# bolid-power-dcdc-ldo.net
KiCad netlist of a schematic drawn in Altium Designer
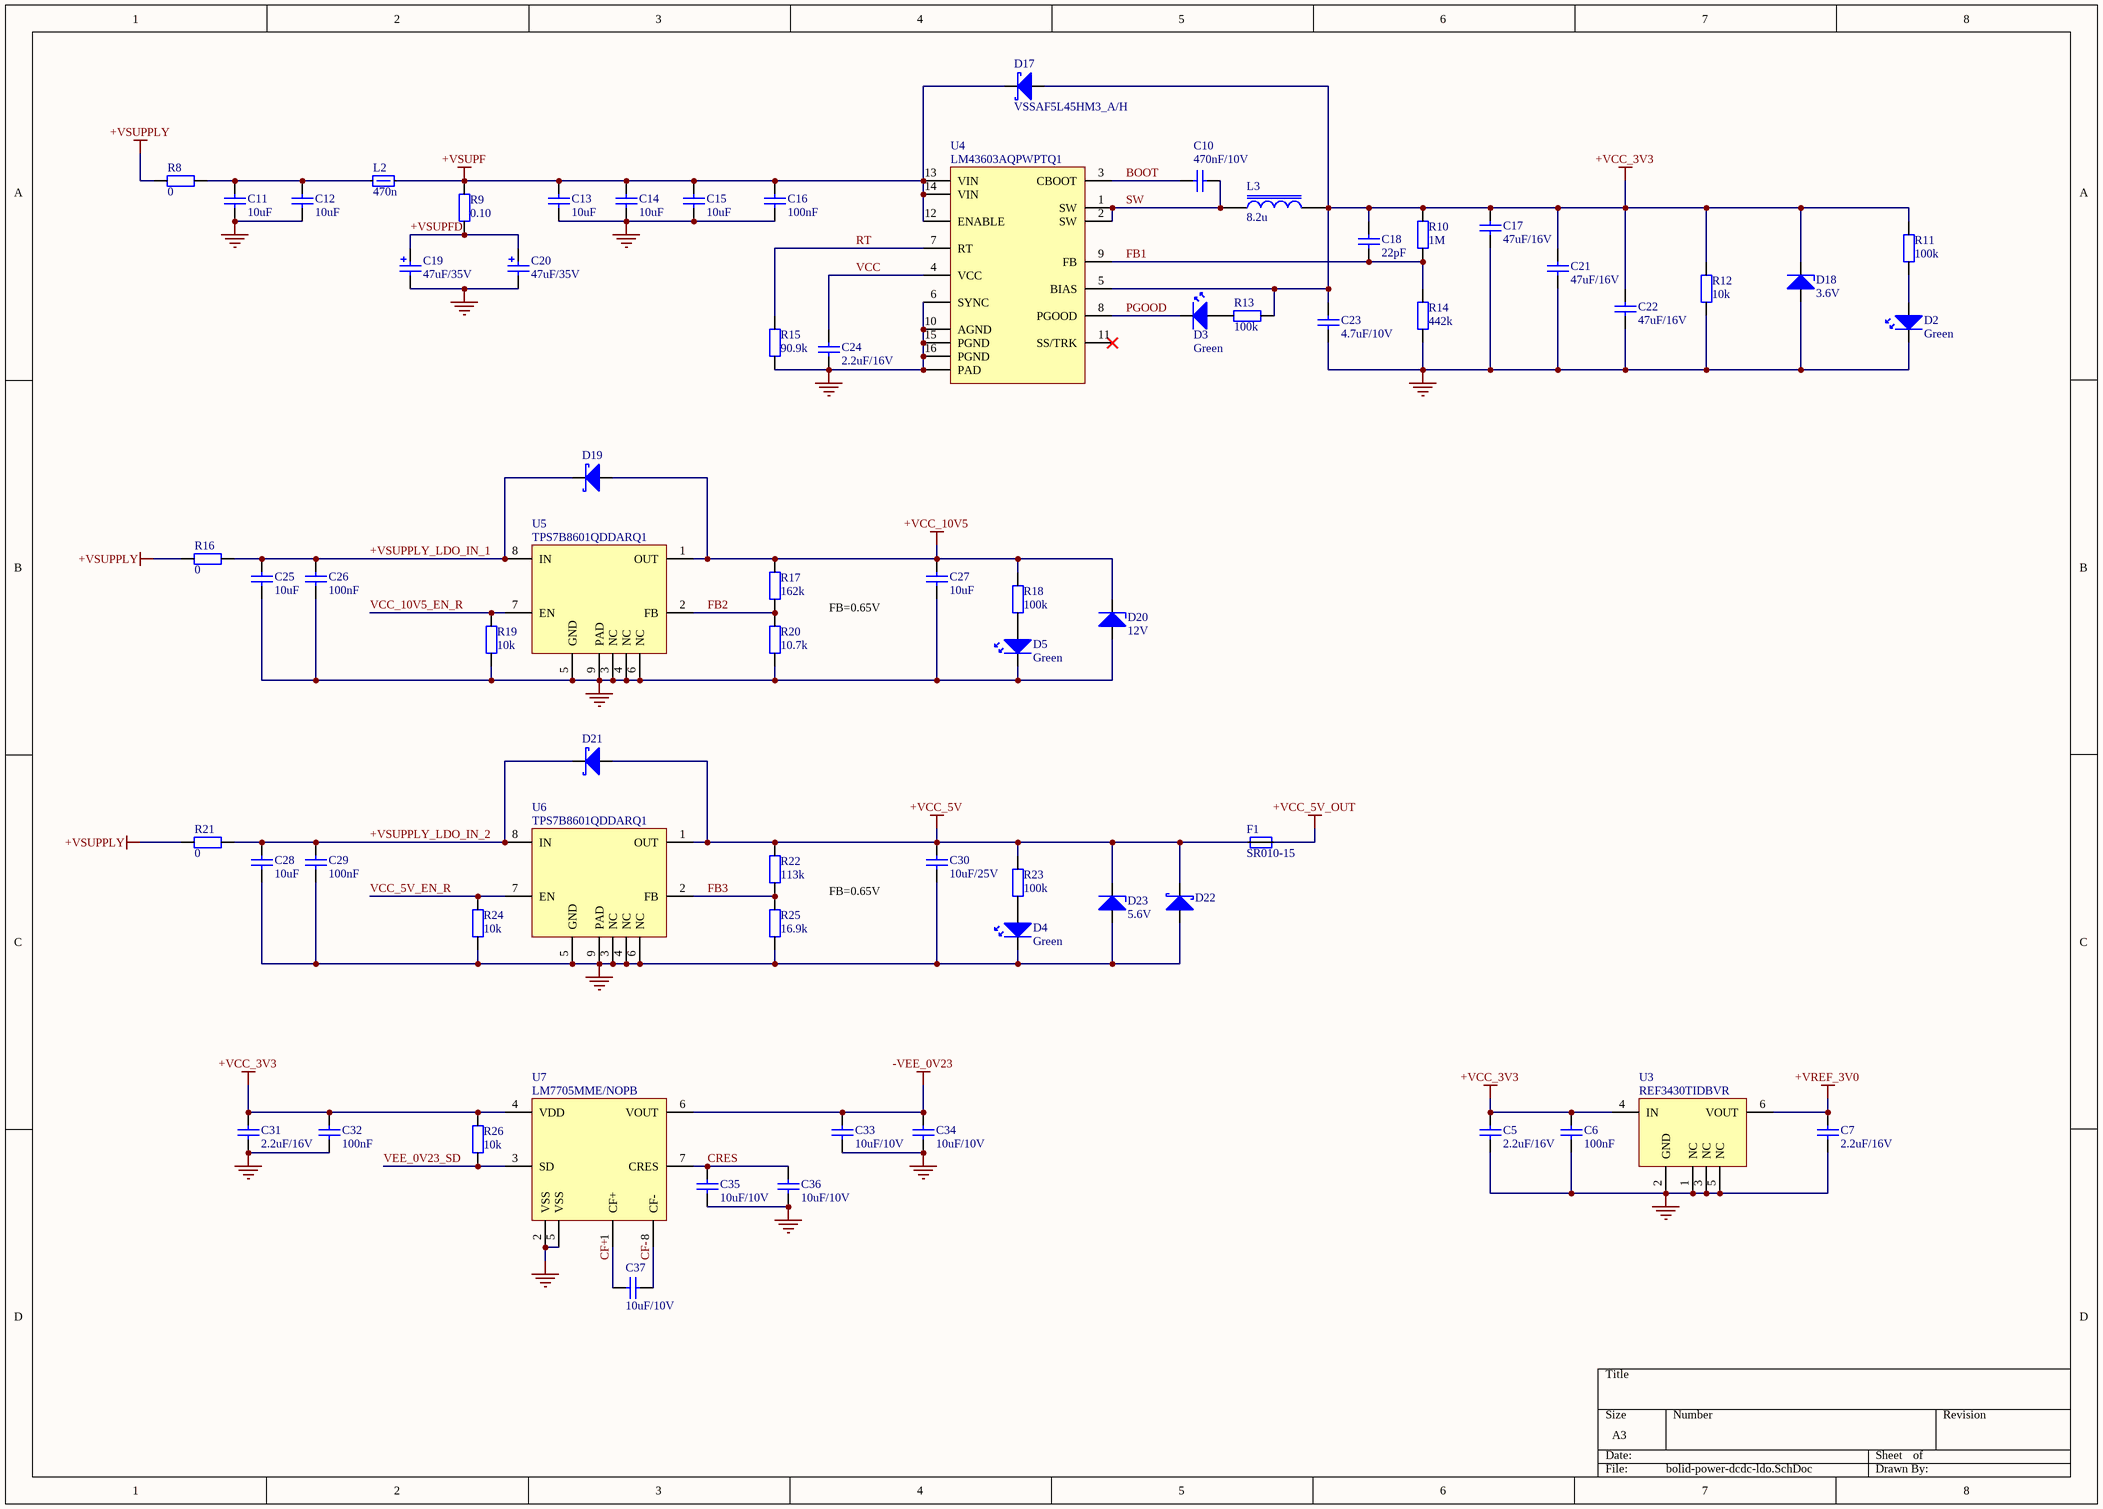
[diagram p0: bolid-power-dcdc-ldo.SchDoc]

(export (version "E")
  (design (tool "Eeschema 10.0.6"))
  (components
    (comp (ref "C5")
      (value "EMK107BB7225MA-T")
      (footprint "C0603-CAPC162X80X95L35N")
      (description "MLCC 0603 (1608) 2.2uF 20% 16V X7R")
      (fields
        (field (name "MANUFACTURER") "Taiyo Yuden")
        (field (name "TOLERANCE") "20 %")
        (field (name "VALUE DISPLAYED") "2.2uF/16V")
      )
      (libsource (lib "capacitors2") (part "EMK107BB7225MA-T"))
    )
    (comp (ref "C6")
      (value "GRM155R71H104KE14D")
      (footprint "C0402-CAPC100X50X55L22 - Tayio Yuden TDK")
      (description "MLCC 0402 (1005) 100nF 10% 50V X7R")
      (fields
        (field (name "MANUFACTURER") "Murata Electronics")
        (field (name "TOLERANCE") "10 %")
        (field (name "VALUE DISPLAYED") "100nF")
      )
      (libsource (lib "capacitors2") (part "GRM155R71H104KE14D"))
    )
    (comp (ref "C7")
      (value "EMK107BB7225MA-T")
      (footprint "C0603-CAPC162X80X95L35N")
      (description "MLCC 0603 (1608) 2.2uF 20% 16V X7R")
      (fields
        (field (name "MANUFACTURER") "Taiyo Yuden")
        (field (name "TOLERANCE") "20 %")
        (field (name "VALUE DISPLAYED") "2.2uF/16V")
      )
      (libsource (lib "capacitors2") (part "EMK107BB7225MA-T"))
    )
    (comp (ref "C10")
      (value "GRM155R71A474KE01D")
      (footprint "C0402-CAPC100X50X55L22 - Tayio Yuden TDK")
      (description "MLCC 0402 (1005) 470nF 10% 10V X7R")
      (fields
        (field (name "MANUFACTURER") "Murata Electronics")
        (field (name "TOLERANCE") "10 %")
        (field (name "VALUE DISPLAYED") "470nF/10V")
      )
      (libsource (lib "capacitors2") (part "GRM155R71A474KE01D"))
    )
    (comp (ref "C11")
      (value "C1210C106K5RACTU")
      (footprint "C1210-CAPC320X250X280L55N - Kemet")
      (description "MLCC 1210 (3225) 10uF 10% 50V X7R")
      (fields
        (field (name "MANUFACTURER") "KEMET")
        (field (name "TOLERANCE") "10 %")
        (field (name "VALUE DISPLAYED") "10uF")
      )
      (libsource (lib "capacitors2") (part "C1210C106K5RACTU"))
    )
    (comp (ref "C12")
      (value "C1210C106K5RACTU")
      (footprint "C1210-CAPC320X250X280L55N - Kemet")
      (description "MLCC 1210 (3225) 10uF 10% 50V X7R")
      (fields
        (field (name "MANUFACTURER") "KEMET")
        (field (name "TOLERANCE") "10 %")
        (field (name "VALUE DISPLAYED") "10uF")
      )
      (libsource (lib "capacitors2") (part "C1210C106K5RACTU"))
    )
    (comp (ref "C13")
      (value "C1210C106K5RACTU")
      (footprint "C1210-CAPC320X250X280L55N - Kemet")
      (description "MLCC 1210 (3225) 10uF 10% 50V X7R")
      (fields
        (field (name "MANUFACTURER") "KEMET")
        (field (name "TOLERANCE") "10 %")
        (field (name "VALUE DISPLAYED") "10uF")
      )
      (libsource (lib "capacitors2") (part "C1210C106K5RACTU"))
    )
    (comp (ref "C14")
      (value "C1210C106K5RACTU")
      (footprint "C1210-CAPC320X250X280L55N - Kemet")
      (description "MLCC 1210 (3225) 10uF 10% 50V X7R")
      (fields
        (field (name "MANUFACTURER") "KEMET")
        (field (name "TOLERANCE") "10 %")
        (field (name "VALUE DISPLAYED") "10uF")
      )
      (libsource (lib "capacitors2") (part "C1210C106K5RACTU"))
    )
    (comp (ref "C15")
      (value "C1210C106K5RACTU")
      (footprint "C1210-CAPC320X250X280L55N - Kemet")
      (description "MLCC 1210 (3225) 10uF 10% 50V X7R")
      (fields
        (field (name "MANUFACTURER") "KEMET")
        (field (name "TOLERANCE") "10 %")
        (field (name "VALUE DISPLAYED") "10uF")
      )
      (libsource (lib "capacitors2") (part "C1210C106K5RACTU"))
    )
    (comp (ref "C16")
      (value "GRM155R71H104KE14D")
      (footprint "C0402-CAPC100X50X55L22 - Tayio Yuden TDK")
      (description "MLCC 0402 (1005) 100nF 10% 50V X7R")
      (fields
        (field (name "MANUFACTURER") "Murata Electronics")
        (field (name "TOLERANCE") "10 %")
        (field (name "VALUE DISPLAYED") "100nF")
      )
      (libsource (lib "capacitors2") (part "GRM155R71H104KE14D"))
    )
    (comp (ref "C17")
      (value "EMK325BJ476MM-P")
      (footprint "C1210-CAPC320X250X280L55N - Kemet")
      (description "MLCC 1210 (3225) 47.0uF 20% 16V X5R")
      (fields
        (field (name "MANUFACTURER") "Taiyo Yuden")
        (field (name "TOLERANCE") "20 %")
        (field (name "VALUE DISPLAYED") "47uF/16V")
      )
      (libsource (lib "capacitors2") (part "EMK325BJ476MM-P"))
    )
    (comp (ref "C18")
      (value "GCM1555C1H220JA16D")
      (footprint "C0402-CAPC100X50X55L22 - Tayio Yuden TDK")
      (description "MLCC 0402 (1005) 22pF 5% 50V C0G (NP0)")
      (fields
        (field (name "MANUFACTURER") "Murata Electronics")
        (field (name "TOLERANCE") "5 %")
        (field (name "VALUE DISPLAYED") "22pF")
      )
      (libsource (lib "capacitors2") (part "GCM1555C1H220JA16D"))
    )
    (comp (ref "C19")
      (value "T495X476K035ATE300")
      (footprint "C7374-43-CAPPM730X430X430L130X240N - Kemet Case X")
      (description "TANT 2917 (7343) 47uF 10% 35V Tantalum Kemet Case X")
      (fields
        (field (name "MANUFACTURER") "KEMET")
        (field (name "TOLERANCE") "10 %")
        (field (name "VALUE DISPLAYED") "47uF/35V")
      )
      (libsource (lib "capacitors2") (part "T495X476K035ATE300"))
    )
    (comp (ref "C20")
      (value "T495X476K035ATE300")
      (footprint "C7374-43-CAPPM730X430X430L130X240N - Kemet Case X")
      (description "TANT 2917 (7343) 47uF 10% 35V Tantalum Kemet Case X")
      (fields
        (field (name "MANUFACTURER") "KEMET")
        (field (name "TOLERANCE") "10 %")
        (field (name "VALUE DISPLAYED") "47uF/35V")
      )
      (libsource (lib "capacitors2") (part "T495X476K035ATE300"))
    )
    (comp (ref "C21")
      (value "EMK325BJ476MM-P")
      (footprint "C1210-CAPC320X250X280L55N - Kemet")
      (description "MLCC 1210 (3225) 47.0uF 20% 16V X5R")
      (fields
        (field (name "MANUFACTURER") "Taiyo Yuden")
        (field (name "TOLERANCE") "20 %")
        (field (name "VALUE DISPLAYED") "47uF/16V")
      )
      (libsource (lib "capacitors2") (part "EMK325BJ476MM-P"))
    )
    (comp (ref "C22")
      (value "EMK325BJ476MM-P")
      (footprint "C1210-CAPC320X250X280L55N - Kemet")
      (description "MLCC 1210 (3225) 47.0uF 20% 16V X5R")
      (fields
        (field (name "MANUFACTURER") "Taiyo Yuden")
        (field (name "TOLERANCE") "20 %")
        (field (name "VALUE DISPLAYED") "47uF/16V")
      )
      (libsource (lib "capacitors2") (part "EMK325BJ476MM-P"))
    )
    (comp (ref "C23")
      (value "C1005X5R1A475M050BC")
      (footprint "C0402-CAPC100X50X55L22 - Tayio Yuden TDK")
      (description "MLCC 0402 (1005) 4.7uF 20% 10V X5R")
      (fields
        (field (name "MANUFACTURER") "TDK")
        (field (name "TOLERANCE") "20 %")
        (field (name "VALUE DISPLAYED") "4.7uF/10V")
      )
      (libsource (lib "capacitors2") (part "C1005X5R1A475M050BC"))
    )
    (comp (ref "C24")
      (value "EMK107BB7225MA-T")
      (footprint "C0603-CAPC162X80X95L35N")
      (description "MLCC 0603 (1608) 2.2uF 20% 16V X7R")
      (fields
        (field (name "MANUFACTURER") "Taiyo Yuden")
        (field (name "TOLERANCE") "20 %")
        (field (name "VALUE DISPLAYED") "2.2uF/16V")
      )
      (libsource (lib "capacitors2") (part "EMK107BB7225MA-T"))
    )
    (comp (ref "C25")
      (value "C1210C106K5RACTU")
      (footprint "C1210-CAPC320X250X280L55N - Kemet")
      (description "MLCC 1210 (3225) 10uF 10% 50V X7R")
      (fields
        (field (name "MANUFACTURER") "KEMET")
        (field (name "TOLERANCE") "10 %")
        (field (name "VALUE DISPLAYED") "10uF")
      )
      (libsource (lib "capacitors2") (part "C1210C106K5RACTU"))
    )
    (comp (ref "C26")
      (value "GRM155R71H104KE14D")
      (footprint "C0402-CAPC100X50X55L22 - Tayio Yuden TDK")
      (description "MLCC 0402 (1005) 100nF 10% 50V X7R")
      (fields
        (field (name "MANUFACTURER") "Murata Electronics")
        (field (name "TOLERANCE") "10 %")
        (field (name "VALUE DISPLAYED") "100nF")
      )
      (libsource (lib "capacitors2") (part "GRM155R71H104KE14D"))
    )
    (comp (ref "C27")
      (value "C1210C106K5RACTU")
      (footprint "C1210-CAPC320X250X280L55N - Kemet")
      (description "MLCC 1210 (3225) 10uF 10% 50V X7R")
      (fields
        (field (name "MANUFACTURER") "KEMET")
        (field (name "TOLERANCE") "10 %")
        (field (name "VALUE DISPLAYED") "10uF")
      )
      (libsource (lib "capacitors2") (part "C1210C106K5RACTU"))
    )
    (comp (ref "C28")
      (value "C1210C106K5RACTU")
      (footprint "C1210-CAPC320X250X280L55N - Kemet")
      (description "MLCC 1210 (3225) 10uF 10% 50V X7R")
      (fields
        (field (name "MANUFACTURER") "KEMET")
        (field (name "TOLERANCE") "10 %")
        (field (name "VALUE DISPLAYED") "10uF")
      )
      (libsource (lib "capacitors2") (part "C1210C106K5RACTU"))
    )
    (comp (ref "C29")
      (value "GRM155R71H104KE14D")
      (footprint "C0402-CAPC100X50X55L22 - Tayio Yuden TDK")
      (description "MLCC 0402 (1005) 100nF 10% 50V X7R")
      (fields
        (field (name "MANUFACTURER") "Murata Electronics")
        (field (name "TOLERANCE") "10 %")
        (field (name "VALUE DISPLAYED") "100nF")
      )
      (libsource (lib "capacitors2") (part "GRM155R71H104KE14D"))
    )
    (comp (ref "C30")
      (value "TMK316AB7106KL-T")
      (footprint "C1206-CAPC320X160X190L65N - Murata")
      (description "MLCC 1206 (3216) 10uF 10% 25V X7R")
      (fields
        (field (name "MANUFACTURER") "Taiyo Yuden")
        (field (name "TOLERANCE") "10 %")
        (field (name "VALUE DISPLAYED") "10uF/25V")
      )
      (libsource (lib "capacitors2") (part "TMK316AB7106KL-T"))
    )
    (comp (ref "C31")
      (value "EMK107BB7225MA-T")
      (footprint "C0603-CAPC162X80X95L35N")
      (description "MLCC 0603 (1608) 2.2uF 20% 16V X7R")
      (fields
        (field (name "MANUFACTURER") "Taiyo Yuden")
        (field (name "TOLERANCE") "20 %")
        (field (name "VALUE DISPLAYED") "2.2uF/16V")
      )
      (libsource (lib "capacitors2") (part "EMK107BB7225MA-T"))
    )
    (comp (ref "C32")
      (value "GRM155R71H104KE14D")
      (footprint "C0402-CAPC100X50X55L22 - Tayio Yuden TDK")
      (description "MLCC 0402 (1005) 100nF 10% 50V X7R")
      (fields
        (field (name "MANUFACTURER") "Murata Electronics")
        (field (name "TOLERANCE") "10 %")
        (field (name "VALUE DISPLAYED") "100nF")
      )
      (libsource (lib "capacitors2") (part "GRM155R71H104KE14D"))
    )
    (comp (ref "C33")
      (value "GRM21BR71A106KA73K")
      (footprint "C0805-CAPC200X125X135L50N - Taiyo YudenN")
      (description "MLCC 0805 (2012) 10uF 10% 10V X7R")
      (fields
        (field (name "MANUFACTURER") "Murata Electronics")
        (field (name "TOLERANCE") "10 %")
        (field (name "VALUE DISPLAYED") "10uF/10V")
      )
      (libsource (lib "capacitors2") (part "GRM21BR71A106KA73K"))
    )
    (comp (ref "C34")
      (value "GRM21BR71A106KA73K")
      (footprint "C0805-CAPC200X125X135L50N - Taiyo YudenN")
      (description "MLCC 0805 (2012) 10uF 10% 10V X7R")
      (fields
        (field (name "MANUFACTURER") "Murata Electronics")
        (field (name "TOLERANCE") "10 %")
        (field (name "VALUE DISPLAYED") "10uF/10V")
      )
      (libsource (lib "capacitors2") (part "GRM21BR71A106KA73K"))
    )
    (comp (ref "C35")
      (value "GRM21BR71A106KA73K")
      (footprint "C0805-CAPC200X125X135L50N - Taiyo YudenN")
      (description "MLCC 0805 (2012) 10uF 10% 10V X7R")
      (fields
        (field (name "MANUFACTURER") "Murata Electronics")
        (field (name "TOLERANCE") "10 %")
        (field (name "VALUE DISPLAYED") "10uF/10V")
      )
      (libsource (lib "capacitors2") (part "GRM21BR71A106KA73K"))
    )
    (comp (ref "C36")
      (value "GRM21BR71A106KA73K")
      (footprint "C0805-CAPC200X125X135L50N - Taiyo YudenN")
      (description "MLCC 0805 (2012) 10uF 10% 10V X7R")
      (fields
        (field (name "MANUFACTURER") "Murata Electronics")
        (field (name "TOLERANCE") "10 %")
        (field (name "VALUE DISPLAYED") "10uF/10V")
      )
      (libsource (lib "capacitors2") (part "GRM21BR71A106KA73K"))
    )
    (comp (ref "C37")
      (value "GRM21BR71A106KA73K")
      (footprint "C0805-CAPC200X125X135L50N - Taiyo YudenN")
      (description "MLCC 0805 (2012) 10uF 10% 10V X7R")
      (fields
        (field (name "MANUFACTURER") "Murata Electronics")
        (field (name "TOLERANCE") "10 %")
        (field (name "VALUE DISPLAYED") "10uF/10V")
      )
      (libsource (lib "capacitors2") (part "GRM21BR71A106KA73K"))
    )
    (comp (ref "D2")
      (value "150060GS75000")
      (footprint "D0603 DIONC166X84X36L42N Littelfuse")
      (description "LED 0603 (1608) Green")
      (fields (field (name "MANUFACTURER") "Wurth Elektronik") (field (name "ILLUMINATION COLOR") "Green"))
      (libsource (lib "semiconductors2") (part "150060GS75000"))
    )
    (comp (ref "D3")
      (value "150060GS75000")
      (footprint "D0603 DIONC166X84X36L42N Littelfuse")
      (description "LED 0603 (1608) Green")
      (fields (field (name "MANUFACTURER") "Wurth Elektronik") (field (name "ILLUMINATION COLOR") "Green"))
      (libsource (lib "semiconductors2") (part "150060GS75000"))
    )
    (comp (ref "D4")
      (value "150060GS75000")
      (footprint "D0603 DIONC166X84X36L42N Littelfuse")
      (description "LED 0603 (1608) Green")
      (fields (field (name "MANUFACTURER") "Wurth Elektronik") (field (name "ILLUMINATION COLOR") "Green"))
      (libsource (lib "semiconductors2") (part "150060GS75000"))
    )
    (comp (ref "D5")
      (value "150060GS75000")
      (footprint "D0603 DIONC166X84X36L42N Littelfuse")
      (description "LED 0603 (1608) Green")
      (fields (field (name "MANUFACTURER") "Wurth Elektronik") (field (name "ILLUMINATION COLOR") "Green"))
      (libsource (lib "semiconductors2") (part "150060GS75000"))
    )
    (comp (ref "D17")
      (value "VSSAF5L45HM3_A/H")
      (footprint "DO-221AC SlimSMA SODFL520X260X100L97X135N - Vishay")
      (description "Schottky Rectifier Diode, 5A, Do-221Ac-2 Rohs Compliant: Yes ¦Vishay VSSAF5L45HM3_A/H")
      (fields (field (name "MANUFACTURER") "Vishay"))
      (libsource (lib "semiconductors2") (part "VSSAF5L45HM3_A/H"))
    )
    (comp (ref "D18")
      (value "BZX84-B3V6,215")
      (footprint "SOT23 (TO-236AB) 04-11-04 SOT95P230X110-3N - Nexperia")
      (description "Zener Diode Single 3.6V 2% 90Ohm 250mW Automotive 3-Pin SOT-23 T/R")
      (fields
        (field (name "MANUFACTURER") "NXP Semiconductors")
        (field (name "TOLERANCE") "2%")
        (field (name "ZENER VOLTAGE") "3.6V")
      )
      (libsource (lib "semiconductors2") (part "BZX84-B3V6,215"))
    )
    (comp (ref "D19")
      (value "MBR0530T3G")
      (footprint "SOD-123-2L SOD375X160X128L32X60N - Fairchild")
      (description "ON Semi MBR0530T3G; SMT Schottky Diode; 30V 500mA; 2-Pin SOD-123")
      (fields (field (name "MANUFACTURER") "ON Semiconductor"))
      (libsource (lib "semiconductors2") (part "MBR0530T3G"))
    )
    (comp (ref "D20")
      (value "BZX84-C12,215")
      (footprint "SOT23 (TO-236AB) 04-11-04 SOT95P230X110-3N - Nexperia")
      (description "Diodes - Zener - Single Diode SOT-23 (TO-236AB) 250mW 12V Surface Mount")
      (fields (field (name "MANUFACTURER") "Nexperia") (field (name "ZENER VOLTAGE") "12V"))
      (libsource (lib "semiconductors2") (part "BZX84-C12,215"))
    )
    (comp (ref "D21")
      (value "MBR0530T3G")
      (footprint "SOD-123-2L SOD375X160X128L32X60N - Fairchild")
      (description "ON Semi MBR0530T3G; SMT Schottky Diode; 30V 500mA; 2-Pin SOD-123")
      (fields (field (name "MANUFACTURER") "ON Semiconductor"))
      (libsource (lib "semiconductors2") (part "MBR0530T3G"))
    )
    (comp (ref "D22")
      (value "MBR0530T3G")
      (footprint "SOD-123-2L SOD375X160X128L32X60N - Fairchild")
      (description "ON Semi MBR0530T3G; SMT Schottky Diode; 30V 500mA; 2-Pin SOD-123")
      (fields (field (name "MANUFACTURER") "ON Semiconductor"))
      (libsource (lib "semiconductors2") (part "MBR0530T3G"))
    )
    (comp (ref "D23")
      (value "BZX84-B5V6,215")
      (footprint "SOT23 (TO-236AB) 04-11-04 SOT95P230X110-3N - Nexperia")
      (description "Zener Diode, 5.6V V(Z), 2%, 0.25W, Silicon, Unidirectional, TO-236AB")
      (fields (field (name "MANUFACTURER") "Nexperia") (field (name "ZENER VOLTAGE") "5.6V"))
      (libsource (lib "semiconductors2") (part "BZX84-B5V6,215"))
    )
    (comp (ref "F1")
      (value "SR010-15")
      (footprint "RESC2214X10N - SR010-15")
      (description "PTC Fuse Hold Current 0.10A, Trip Current 0.30A VMax 15V")
      (fields (field (name "MANUFACTURER") "Excel Cell"))
      (libsource (lib "misc2") (part "SR010-15"))
    )
    (comp (ref "L2")
      (value "470n")
      (footprint "MURATA DFE252012F 1008 INDC250X200X120L60N")
      (description "Inductor Power Chip Shielded Wirewound 0.47uH 20% 1MHz Metal 4.9A 0.023Ohm DCR 1008 T/R")
      (fields
        (field (name "MANUFACTURER") "Murata")
        (field (name "MANUFACTURER PART NUMBER") "DFE252012F-R47M=P2")
      )
      (libsource (lib "inductors2") (part "DFE252012F-R47M=P2"))
    )
    (comp (ref "L3")
      (value "8.2u")
      (footprint "Coilcraft XAL50xx")
      (description "Fixed Inductors 8.2uH 20% 6.1A 34.95mOhms AEC-Q200")
      (fields
        (field (name "MANUFACTURER") "Coilcraft")
        (field (name "MANUFACTURER PART NUMBER") "XAL5050-822MEB")
      )
      (libsource (lib "inductors2") (part "XAL5050-822MEB"))
    )
    (comp (ref "R8")
      (value "0")
      (footprint "R0603-RESC160X80X55L30N")
      (description "RES 0603 (1608) 0.00 ohm 1% 0.100W 75V Thick Film")
      (fields
        (field (name "MANUFACTURER") "Yageo")
        (field (name "MANUFACTURER PART NUMBER") "RC0603FR-070RL")
      )
      (libsource (lib "resistors2") (part "RC0603FR-070RL"))
    )
    (comp (ref "R9")
      (value "0.10")
      (footprint "R0603-RESC160X80X55L30N")
      (description "RES 0603 (1608) 0.10 ohm 1% 0.100W Thick Film")
      (fields
        (field (name "MANUFACTURER") "Panasonic")
        (field (name "MANUFACTURER PART NUMBER") "ERJ-3RSFR10V")
      )
      (libsource (lib "resistors2") (part "ERJ-3RSFR10V"))
    )
    (comp (ref "R10")
      (value "1M")
      (footprint "R0402-RESC100X50X40L22N")
      (description "RES 0402 (1005) 1.00M 1% 0.0625W 50V Thick Film")
      (fields
        (field (name "MANUFACTURER") "YAGEO")
        (field (name "MANUFACTURER PART NUMBER") "AC0402FR-071ML")
      )
      (libsource (lib "resistors2") (part "AC0402FR-071ML"))
    )
    (comp (ref "R11")
      (value "100k")
      (footprint "R0402-RESC100X50X40L22N")
      (description "RES 0402 (1005) 100.0k 1% 0.0625W 50V Thick Film")
      (fields
        (field (name "MANUFACTURER") "Yageo")
        (field (name "MANUFACTURER PART NUMBER") "RC0402FR-07100KL")
      )
      (libsource (lib "") (part "RC0402FR-07100KL_1"))
    )
    (comp (ref "R12")
      (value "10k")
      (footprint "R0402-RESC100X50X40L22N")
      (description "RES 0402 (1005) 10.0k 1% 0.0625W 50V Thick Film")
      (fields
        (field (name "MANUFACTURER") "Yageo")
        (field (name "MANUFACTURER PART NUMBER") "RC0402FR-0710KL")
      )
      (libsource (lib "resistors2") (part "RC0402FR-0710KL"))
    )
    (comp (ref "R13")
      (value "100k")
      (footprint "R0402-RESC100X50X40L22N")
      (description "RES 0402 (1005) 100.0k 1% 0.0625W 50V Thick Film")
      (fields
        (field (name "MANUFACTURER") "Yageo")
        (field (name "MANUFACTURER PART NUMBER") "RC0402FR-07100KL")
      )
      (libsource (lib "resistors2") (part "RC0402FR-07100KL"))
    )
    (comp (ref "R14")
      (value "442k")
      (footprint "R0402-RESC100X50X40L22N")
      (description "RES 0402 (1005) 442.0k 1% 0.100W 50V Thick Film")
      (fields
        (field (name "MANUFACTURER") "Panasonic")
        (field (name "MANUFACTURER PART NUMBER") "ERJ-2RKF4423X")
      )
      (libsource (lib "resistors2") (part "ERJ-2RKF4423X"))
    )
    (comp (ref "R15")
      (value "90.9k")
      (footprint "R0402-RESC100X50X40L22N")
      (description "RES 0402 (1005) 90.9k 1% 0.0625W 50V Thick Film")
      (fields
        (field (name "MANUFACTURER") "YAGEO")
        (field (name "MANUFACTURER PART NUMBER") "RC0402FR-0790K9L")
      )
      (libsource (lib "resistors2") (part "RC0402FR-0790K9L"))
    )
    (comp (ref "R16")
      (value "0")
      (footprint "R0603-RESC160X80X55L30N")
      (description "RES 0603 (1608) 0.00 ohm 1% 0.100W 75V Thick Film")
      (fields
        (field (name "MANUFACTURER") "Yageo")
        (field (name "MANUFACTURER PART NUMBER") "RC0603FR-070RL")
      )
      (libsource (lib "resistors2") (part "RC0603FR-070RL"))
    )
    (comp (ref "R17")
      (value "162k")
      (footprint "R0402-RESC100X50X40L22N")
      (description "RES 0402 (1005) 162.0k 1% 0.125W 50V Thick Film")
      (fields
        (field (name "MANUFACTURER") "Yageo")
        (field (name "MANUFACTURER PART NUMBER") "AC0402FR-07162KL")
      )
      (libsource (lib "resistors2") (part "AC0402FR-07162KL"))
    )
    (comp (ref "R18")
      (value "100k")
      (footprint "R0402-RESC100X50X40L22N")
      (description "RES 0402 (1005) 100.0k 1% 0.0625W 50V Thick Film")
      (fields
        (field (name "MANUFACTURER") "Yageo")
        (field (name "MANUFACTURER PART NUMBER") "RC0402FR-07100KL")
      )
      (libsource (lib "") (part "RC0402FR-07100KL_1"))
    )
    (comp (ref "R19")
      (value "10k")
      (footprint "R0402-RESC100X50X40L22N")
      (description "RES 0402 (1005) 10.0k 1% 0.0625W 50V Thick Film")
      (fields
        (field (name "MANUFACTURER") "Yageo")
        (field (name "MANUFACTURER PART NUMBER") "RC0402FR-0710KL")
      )
      (libsource (lib "resistors2") (part "RC0402FR-0710KL"))
    )
    (comp (ref "R20")
      (value "10.7k")
      (footprint "R0402-RESC100X50X40L22N")
      (description "RES 0402 (1005) 10.7k 1% 0.125W 50V Thick Film")
      (fields
        (field (name "MANUFACTURER") "Yageo")
        (field (name "MANUFACTURER PART NUMBER") "AC0402FR-0710K7L")
      )
      (libsource (lib "resistors2") (part "AC0402FR-0710K7L"))
    )
    (comp (ref "R21")
      (value "0")
      (footprint "R0603-RESC160X80X55L30N")
      (description "RES 0603 (1608) 0.00 ohm 1% 0.100W 75V Thick Film")
      (fields
        (field (name "MANUFACTURER") "Yageo")
        (field (name "MANUFACTURER PART NUMBER") "RC0603FR-070RL")
      )
      (libsource (lib "resistors2") (part "RC0603FR-070RL"))
    )
    (comp (ref "R22")
      (value "113k")
      (footprint "R0402-RESC100X50X40L22N")
      (description "RES 0402 (1005) 113.0k 1% 0.0625W 50V Thick Film")
      (fields
        (field (name "MANUFACTURER") "Yageo")
        (field (name "MANUFACTURER PART NUMBER") "RC0402FR-07113KL")
      )
      (libsource (lib "resistors2") (part "RC0402FR-07113KL"))
    )
    (comp (ref "R23")
      (value "100k")
      (footprint "R0402-RESC100X50X40L22N")
      (description "RES 0402 (1005) 100.0k 1% 0.0625W 50V Thick Film")
      (fields
        (field (name "MANUFACTURER") "Yageo")
        (field (name "MANUFACTURER PART NUMBER") "RC0402FR-07100KL")
      )
      (libsource (lib "") (part "RC0402FR-07100KL_1"))
    )
    (comp (ref "R24")
      (value "10k")
      (footprint "R0402-RESC100X50X40L22N")
      (description "RES 0402 (1005) 10.0k 1% 0.0625W 50V Thick Film")
      (fields
        (field (name "MANUFACTURER") "Yageo")
        (field (name "MANUFACTURER PART NUMBER") "RC0402FR-0710KL")
      )
      (libsource (lib "resistors2") (part "RC0402FR-0710KL"))
    )
    (comp (ref "R25")
      (value "16.9k")
      (footprint "R0402-RESC100X50X40L22N")
      (description "RES 0402 (1005) 16.9k 1% 0.0625W 50V Thick Film")
      (fields
        (field (name "MANUFACTURER") "Yageo")
        (field (name "MANUFACTURER PART NUMBER") "RC0402FR-0716K9L")
      )
      (libsource (lib "resistors2") (part "RC0402FR-0716K9L"))
    )
    (comp (ref "R26")
      (value "10k")
      (footprint "R0402-RESC100X50X40L22N")
      (description "RES 0402 (1005) 10.0k 1% 0.0625W 50V Thick Film")
      (fields
        (field (name "MANUFACTURER") "Yageo")
        (field (name "MANUFACTURER PART NUMBER") "RC0402FR-0710KL")
      )
      (libsource (lib "resistors2") (part "RC0402FR-0710KL"))
    )
    (comp (ref "U3")
      (value "REF3430TIDBVR")
      (footprint "TI SOT23 DBV0006A SOT23-6P95_280X145L45X37N")
      (description "3-V, low-drift, low-power, small-footprint series voltage reference 6-SOT-23 -40 to 125")
      (fields (field (name "MANUFACTURER") "Texas Instruments"))
      (libsource (lib "ics2") (part "REF3430TIDBVR"))
    )
    (comp (ref "U4")
      (value "LM43603AQPWPTQ1")
      (footprint "TI TSSOP16 PWP0016G SOP17P65_500X640X120L62X24T300X210N - NO PASTE REDUCTION")
      (description "Automotive Qualified 3.5V to 36V, 3A Synchronous Step-Down Voltage Converter 16-HTSSOP -40 to 125")
      (fields (field (name "MANUFACTURER") "Texas Instruments"))
      (libsource (lib "ics2") (part "LM43603AQPWPTQ1"))
    )
    (comp (ref "U5")
      (value "TPS7B8601QDDARQ1")
      (footprint "TI SOIC8 DDA0008E-C01 SOIC127P600X170_HS-9N")
      (fields (field (name "MANUFACTURER") "Texas Instruments"))
      (libsource (lib "ics2") (part "TPS7B8601QDDARQ1"))
    )
    (comp (ref "U6")
      (value "TPS7B8601QDDARQ1")
      (footprint "TI SOIC8 DDA0008E-C01 SOIC127P600X170_HS-9N")
      (fields (field (name "MANUFACTURER") "Texas Instruments"))
      (libsource (lib "ics2") (part "TPS7B8601QDDARQ1"))
    )
    (comp (ref "U7")
      (value "LM7705MME/NOPB")
      (footprint "TI VSSOP8 DGK0008A TSOP65P490X110-8N")
      (description "IC SW CAP/INV -230MV 20MA 8MSOP")
      (fields (field (name "MANUFACTURER") "TI National Semiconductor"))
      (libsource (lib "ics2") (part "LM7705MME/NOPB"))
    )
  )
  (nets
    (net (code "1") (name "+VCC_3V3") (class "Default")
      (node (ref "C17") (pin "2") (pinfunction "2_2") (pintype "passive"))
      (node (ref "C18") (pin "2") (pinfunction "2_2") (pintype "passive"))
      (node (ref "C21") (pin "2") (pinfunction "2_2") (pintype "passive"))
      (node (ref "C22") (pin "2") (pinfunction "2_2") (pintype "passive"))
      (node (ref "C23") (pin "2") (pinfunction "2_2") (pintype "passive"))
      (node (ref "C31") (pin "2") (pinfunction "2_2") (pintype "passive"))
      (node (ref "C32") (pin "2") (pinfunction "2_2") (pintype "passive"))
      (node (ref "C5") (pin "2") (pinfunction "2_2") (pintype "passive"))
      (node (ref "C6") (pin "2") (pinfunction "2_2") (pintype "passive"))
      (node (ref "D17") (pin "2") (pinfunction "A_2") (pintype "passive"))
      (node (ref "D18") (pin "3") (pinfunction "K_3") (pintype "passive"))
      (node (ref "L3") (pin "2") (pinfunction "2_2") (pintype "passive"))
      (node (ref "R10") (pin "2") (pinfunction "2_2") (pintype "passive"))
      (node (ref "R11") (pin "2") (pinfunction "2_2") (pintype "passive"))
      (node (ref "R12") (pin "2") (pinfunction "2_2") (pintype "passive"))
      (node (ref "R13") (pin "2") (pinfunction "2_2") (pintype "passive"))
      (node (ref "R26") (pin "2") (pinfunction "2_2") (pintype "passive"))
      (node (ref "U3") (pin "4") (pinfunction "IN_4") (pintype "passive"))
      (node (ref "U4") (pin "5") (pinfunction "BIAS_5") (pintype "passive"))
      (node (ref "U7") (pin "4") (pinfunction "VDD_4") (pintype "passive"))
    )
    (net (code "2") (name "+VCC_5V") (class "Default")
      (node (ref "C30") (pin "2") (pinfunction "2_2") (pintype "passive"))
      (node (ref "D21") (pin "2") (pinfunction "A_2") (pintype "passive"))
      (node (ref "D22") (pin "1") (pinfunction "K_1") (pintype "passive"))
      (node (ref "D23") (pin "3") (pinfunction "K_3") (pintype "passive"))
      (node (ref "F1") (pin "1") (pinfunction "1_1") (pintype "passive"))
      (node (ref "R22") (pin "2") (pinfunction "2_2") (pintype "passive"))
      (node (ref "R23") (pin "2") (pinfunction "2_2") (pintype "passive"))
      (node (ref "U6") (pin "1") (pinfunction "OUT_1") (pintype "passive"))
    )
    (net (code "3") (name "+VCC_5V_OUT") (class "Default")
      (node (ref "F1") (pin "2") (pinfunction "2_2") (pintype "passive"))
    )
    (net (code "4") (name "+VCC_10V5") (class "Default")
      (node (ref "C27") (pin "2") (pinfunction "2_2") (pintype "passive"))
      (node (ref "D19") (pin "2") (pinfunction "A_2") (pintype "passive"))
      (node (ref "D20") (pin "3") (pinfunction "K_3") (pintype "passive"))
      (node (ref "R17") (pin "2") (pinfunction "2_2") (pintype "passive"))
      (node (ref "R18") (pin "2") (pinfunction "2_2") (pintype "passive"))
      (node (ref "U5") (pin "1") (pinfunction "OUT_1") (pintype "passive"))
    )
    (net (code "5") (name "+VREF_3V0") (class "Default")
      (node (ref "C7") (pin "2") (pinfunction "2_2") (pintype "passive"))
      (node (ref "U3") (pin "6") (pinfunction "VOUT_6") (pintype "passive"))
    )
    (net (code "6") (name "+VSUPF") (class "Default")
      (node (ref "C13") (pin "2") (pinfunction "2_2") (pintype "passive"))
      (node (ref "C14") (pin "2") (pinfunction "2_2") (pintype "passive"))
      (node (ref "C15") (pin "2") (pinfunction "2_2") (pintype "passive"))
      (node (ref "C16") (pin "2") (pinfunction "2_2") (pintype "passive"))
      (node (ref "D17") (pin "1") (pinfunction "K_1") (pintype "passive"))
      (node (ref "L2") (pin "2") (pinfunction "2_2") (pintype "passive"))
      (node (ref "R9") (pin "2") (pinfunction "2_2") (pintype "passive"))
      (node (ref "U4") (pin "12") (pinfunction "ENABLE_12") (pintype "passive"))
      (node (ref "U4") (pin "13") (pinfunction "VIN_13") (pintype "passive"))
      (node (ref "U4") (pin "14") (pinfunction "VIN_14") (pintype "passive"))
    )
    (net (code "7") (name "+VSUPPLY") (class "Default")
      (node (ref "R16") (pin "1") (pinfunction "1_1") (pintype "passive"))
      (node (ref "R21") (pin "1") (pinfunction "1_1") (pintype "passive"))
      (node (ref "R8") (pin "1") (pinfunction "1_1") (pintype "passive"))
    )
    (net (code "8") (name "-VEE_0V23") (class "Default")
      (node (ref "C33") (pin "2") (pinfunction "2_2") (pintype "passive"))
      (node (ref "C34") (pin "2") (pinfunction "2_2") (pintype "passive"))
      (node (ref "U7") (pin "6") (pinfunction "VOUT_6") (pintype "passive"))
    )
    (net (code "9") (name "/+VSUPFD") (class "Default")
      (node (ref "C19") (pin "2") (pinfunction "2_2") (pintype "passive"))
      (node (ref "C20") (pin "2") (pinfunction "2_2") (pintype "passive"))
      (node (ref "R9") (pin "1") (pinfunction "1_1") (pintype "passive"))
    )
    (net (code "10") (name "/+VSUPPLY_LDO_IN_1") (class "Default")
      (node (ref "C25") (pin "2") (pinfunction "2_2") (pintype "passive"))
      (node (ref "C26") (pin "2") (pinfunction "2_2") (pintype "passive"))
      (node (ref "D19") (pin "1") (pinfunction "K_1") (pintype "passive"))
      (node (ref "R16") (pin "2") (pinfunction "2_2") (pintype "passive"))
      (node (ref "U5") (pin "8") (pinfunction "IN_8") (pintype "passive"))
    )
    (net (code "11") (name "/+VSUPPLY_LDO_IN_2") (class "Default")
      (node (ref "C28") (pin "2") (pinfunction "2_2") (pintype "passive"))
      (node (ref "C29") (pin "2") (pinfunction "2_2") (pintype "passive"))
      (node (ref "D21") (pin "1") (pinfunction "K_1") (pintype "passive"))
      (node (ref "R21") (pin "2") (pinfunction "2_2") (pintype "passive"))
      (node (ref "U6") (pin "8") (pinfunction "IN_8") (pintype "passive"))
    )
    (net (code "12") (name "/BOOT") (class "Default")
      (node (ref "C10") (pin "1") (pinfunction "1_1") (pintype "passive"))
      (node (ref "U4") (pin "3") (pinfunction "CBOOT_3") (pintype "passive"))
    )
    (net (code "13") (name "/CF+") (class "Default")
      (node (ref "C37") (pin "2") (pinfunction "2_2") (pintype "passive"))
      (node (ref "U7") (pin "1") (pinfunction "CF+_1") (pintype "passive"))
    )
    (net (code "14") (name "/CF-") (class "Default")
      (node (ref "C37") (pin "1") (pinfunction "1_1") (pintype "passive"))
      (node (ref "U7") (pin "8") (pinfunction "CF-_8") (pintype "passive"))
    )
    (net (code "15") (name "/CRES") (class "Default")
      (node (ref "C35") (pin "2") (pinfunction "2_2") (pintype "passive"))
      (node (ref "C36") (pin "2") (pinfunction "2_2") (pintype "passive"))
      (node (ref "U7") (pin "7") (pinfunction "CRES_7") (pintype "passive"))
    )
    (net (code "16") (name "/FB1") (class "Default")
      (node (ref "C18") (pin "1") (pinfunction "1_1") (pintype "passive"))
      (node (ref "R10") (pin "1") (pinfunction "1_1") (pintype "passive"))
      (node (ref "R14") (pin "2") (pinfunction "2_2") (pintype "passive"))
      (node (ref "U4") (pin "9") (pinfunction "FB_9") (pintype "passive"))
    )
    (net (code "17") (name "/FB2") (class "Default")
      (node (ref "R17") (pin "1") (pinfunction "1_1") (pintype "passive"))
      (node (ref "R20") (pin "2") (pinfunction "2_2") (pintype "passive"))
      (node (ref "U5") (pin "2") (pinfunction "FB_2") (pintype "passive"))
    )
    (net (code "18") (name "/FB3") (class "Default")
      (node (ref "R22") (pin "1") (pinfunction "1_1") (pintype "passive"))
      (node (ref "R25") (pin "2") (pinfunction "2_2") (pintype "passive"))
      (node (ref "U6") (pin "2") (pinfunction "FB_2") (pintype "passive"))
    )
    (net (code "19") (name "/PGOOD") (class "Default")
      (node (ref "D3") (pin "1") (pinfunction "K_1") (pintype "passive"))
      (node (ref "U4") (pin "8") (pinfunction "PGOOD_8") (pintype "passive"))
    )
    (net (code "20") (name "/RT") (class "Default")
      (node (ref "R15") (pin "2") (pinfunction "2_2") (pintype "passive"))
      (node (ref "U4") (pin "7") (pinfunction "RT_7") (pintype "passive"))
    )
    (net (code "21") (name "/SW") (class "Default")
      (node (ref "C10") (pin "2") (pinfunction "2_2") (pintype "passive"))
      (node (ref "L3") (pin "1") (pinfunction "1_1") (pintype "passive"))
      (node (ref "U4") (pin "1") (pinfunction "SW_1") (pintype "passive"))
      (node (ref "U4") (pin "2") (pinfunction "SW_2") (pintype "passive"))
    )
    (net (code "22") (name "/VCC") (class "Default")
      (node (ref "C24") (pin "2") (pinfunction "2_2") (pintype "passive"))
      (node (ref "U4") (pin "4") (pinfunction "VCC_4") (pintype "passive"))
    )
    (net (code "23") (name "/VCC_5V_EN_R") (class "Default")
      (node (ref "R24") (pin "2") (pinfunction "2_2") (pintype "passive"))
      (node (ref "U6") (pin "7") (pinfunction "EN_7") (pintype "passive"))
    )
    (net (code "24") (name "/VCC_10V5_EN_R") (class "Default")
      (node (ref "R19") (pin "2") (pinfunction "2_2") (pintype "passive"))
      (node (ref "U5") (pin "7") (pinfunction "EN_7") (pintype "passive"))
    )
    (net (code "25") (name "/VEE_0V23_SD") (class "Default")
      (node (ref "R26") (pin "1") (pinfunction "1_1") (pintype "passive"))
      (node (ref "U7") (pin "3") (pinfunction "SD_3") (pintype "passive"))
    )
    (net (code "26") (name "GND") (class "Default")
      (node (ref "C11") (pin "1") (pinfunction "1_1") (pintype "passive"))
      (node (ref "C12") (pin "1") (pinfunction "1_1") (pintype "passive"))
      (node (ref "C13") (pin "1") (pinfunction "1_1") (pintype "passive"))
      (node (ref "C14") (pin "1") (pinfunction "1_1") (pintype "passive"))
      (node (ref "C15") (pin "1") (pinfunction "1_1") (pintype "passive"))
      (node (ref "C16") (pin "1") (pinfunction "1_1") (pintype "passive"))
      (node (ref "C17") (pin "1") (pinfunction "1_1") (pintype "passive"))
      (node (ref "C19") (pin "1") (pinfunction "1_1") (pintype "passive"))
      (node (ref "C20") (pin "1") (pinfunction "1_1") (pintype "passive"))
      (node (ref "C21") (pin "1") (pinfunction "1_1") (pintype "passive"))
      (node (ref "C22") (pin "1") (pinfunction "1_1") (pintype "passive"))
      (node (ref "C23") (pin "1") (pinfunction "1_1") (pintype "passive"))
      (node (ref "C24") (pin "1") (pinfunction "1_1") (pintype "passive"))
      (node (ref "C25") (pin "1") (pinfunction "1_1") (pintype "passive"))
      (node (ref "C26") (pin "1") (pinfunction "1_1") (pintype "passive"))
      (node (ref "C27") (pin "1") (pinfunction "1_1") (pintype "passive"))
      (node (ref "C28") (pin "1") (pinfunction "1_1") (pintype "passive"))
      (node (ref "C29") (pin "1") (pinfunction "1_1") (pintype "passive"))
      (node (ref "C30") (pin "1") (pinfunction "1_1") (pintype "passive"))
      (node (ref "C31") (pin "1") (pinfunction "1_1") (pintype "passive"))
      (node (ref "C32") (pin "1") (pinfunction "1_1") (pintype "passive"))
      (node (ref "C33") (pin "1") (pinfunction "1_1") (pintype "passive"))
      (node (ref "C34") (pin "1") (pinfunction "1_1") (pintype "passive"))
      (node (ref "C35") (pin "1") (pinfunction "1_1") (pintype "passive"))
      (node (ref "C36") (pin "1") (pinfunction "1_1") (pintype "passive"))
      (node (ref "C5") (pin "1") (pinfunction "1_1") (pintype "passive"))
      (node (ref "C6") (pin "1") (pinfunction "1_1") (pintype "passive"))
      (node (ref "C7") (pin "1") (pinfunction "1_1") (pintype "passive"))
      (node (ref "D18") (pin "1") (pinfunction "A_1") (pintype "passive"))
      (node (ref "D2") (pin "1") (pinfunction "K_1") (pintype "passive"))
      (node (ref "D20") (pin "1") (pinfunction "A_1") (pintype "passive"))
      (node (ref "D22") (pin "2") (pinfunction "A_2") (pintype "passive"))
      (node (ref "D23") (pin "1") (pinfunction "A_1") (pintype "passive"))
      (node (ref "D4") (pin "1") (pinfunction "K_1") (pintype "passive"))
      (node (ref "D5") (pin "1") (pinfunction "K_1") (pintype "passive"))
      (node (ref "R12") (pin "1") (pinfunction "1_1") (pintype "passive"))
      (node (ref "R14") (pin "1") (pinfunction "1_1") (pintype "passive"))
      (node (ref "R15") (pin "1") (pinfunction "1_1") (pintype "passive"))
      (node (ref "R19") (pin "1") (pinfunction "1_1") (pintype "passive"))
      (node (ref "R20") (pin "1") (pinfunction "1_1") (pintype "passive"))
      (node (ref "R24") (pin "1") (pinfunction "1_1") (pintype "passive"))
      (node (ref "R25") (pin "1") (pinfunction "1_1") (pintype "passive"))
      (node (ref "U3") (pin "1") (pinfunction "NC_1") (pintype "passive"))
      (node (ref "U3") (pin "2") (pinfunction "GND_2") (pintype "passive"))
      (node (ref "U3") (pin "3") (pinfunction "NC_3") (pintype "passive"))
      (node (ref "U3") (pin "5") (pinfunction "NC_5") (pintype "passive"))
      (node (ref "U4") (pin "10") (pinfunction "AGND_10") (pintype "passive"))
      (node (ref "U4") (pin "15") (pinfunction "PGND_15") (pintype "passive"))
      (node (ref "U4") (pin "16") (pinfunction "PGND_16") (pintype "passive"))
      (node (ref "U4") (pin "17") (pinfunction "PAD_17") (pintype "passive"))
      (node (ref "U4") (pin "6") (pinfunction "SYNC_6") (pintype "passive"))
      (node (ref "U5") (pin "3") (pinfunction "NC_3") (pintype "passive"))
      (node (ref "U5") (pin "4") (pinfunction "NC_4") (pintype "passive"))
      (node (ref "U5") (pin "5") (pinfunction "GND_5") (pintype "passive"))
      (node (ref "U5") (pin "6") (pinfunction "NC_6") (pintype "passive"))
      (node (ref "U5") (pin "9") (pinfunction "PAD_9") (pintype "passive"))
      (node (ref "U6") (pin "3") (pinfunction "NC_3") (pintype "passive"))
      (node (ref "U6") (pin "4") (pinfunction "NC_4") (pintype "passive"))
      (node (ref "U6") (pin "5") (pinfunction "GND_5") (pintype "passive"))
      (node (ref "U6") (pin "6") (pinfunction "NC_6") (pintype "passive"))
      (node (ref "U6") (pin "9") (pinfunction "PAD_9") (pintype "passive"))
      (node (ref "U7") (pin "2") (pinfunction "VSS_2") (pintype "passive"))
      (node (ref "U7") (pin "5") (pinfunction "VSS_5") (pintype "passive"))
    )
    (net (code "27") (name "Net-(C11-Pad2)") (class "Default")
      (node (ref "C11") (pin "2") (pinfunction "2_2") (pintype "passive"))
      (node (ref "C12") (pin "2") (pinfunction "2_2") (pintype "passive"))
      (node (ref "L2") (pin "1") (pinfunction "1_1") (pintype "passive"))
      (node (ref "R8") (pin "2") (pinfunction "2_2") (pintype "passive"))
    )
    (net (code "28") (name "Net-(D2-A)") (class "Default")
      (node (ref "D2") (pin "2") (pinfunction "A_2") (pintype "passive"))
      (node (ref "R11") (pin "1") (pinfunction "1_1") (pintype "passive"))
    )
    (net (code "29") (name "Net-(D3-A)") (class "Default")
      (node (ref "D3") (pin "2") (pinfunction "A_2") (pintype "passive"))
      (node (ref "R13") (pin "1") (pinfunction "1_1") (pintype "passive"))
    )
    (net (code "30") (name "Net-(D4-A)") (class "Default")
      (node (ref "D4") (pin "2") (pinfunction "A_2") (pintype "passive"))
      (node (ref "R23") (pin "1") (pinfunction "1_1") (pintype "passive"))
    )
    (net (code "31") (name "Net-(D5-A)") (class "Default")
      (node (ref "D5") (pin "2") (pinfunction "A_2") (pintype "passive"))
      (node (ref "R18") (pin "1") (pinfunction "1_1") (pintype "passive"))
    )
    (net (code "32") (name "unconnected-(U4-SS{slash}TRK-Pad11)") (class "Default")
      (node (ref "U4") (pin "11") (pinfunction "SS/TRK_11") (pintype "passive+no_connect"))
    )
  )
)
